# schematic.net
KiCad netlist of a schematic drawn in EAGLE
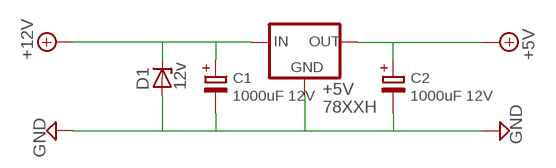
[diagram p0: schematic, sheet 1]

(export (version "E")
  (design (tool "Eeschema 10.0.6"))
  (components
    (comp (ref "+5V")
      (value "78XXH")
      (footprint "eagle-import:TO220BH")
      (libsource (lib "eagle-import") (part "78XXH"))
    )
    (comp (ref "C1")
      (value "1000uF 12V")
      (footprint "eagle-import:CAPD10L5")
      (libsource (lib "eagle-import") (part "CAPD10L5"))
    )
    (comp (ref "C2")
      (value "1000uF 12V")
      (footprint "eagle-import:CAPD10L5")
      (libsource (lib "eagle-import") (part "CAPD10L5"))
    )
    (comp (ref "D1")
      (value "12v")
      (footprint "eagle-import:DO34Z7")
      (libsource (lib "eagle-import") (part "ZENER-DIODEDO34-7"))
    )
  )
  (nets
    (net (code "1") (name "+5V") (class "Default")
      (node (ref "+5V") (pin "S") (pinfunction "OUT_S") (pintype "passive"))
      (node (ref "C2") (pin "1") (pinfunction "+_1") (pintype "passive"))
    )
    (net (code "2") (name "+12V") (class "Default")
      (node (ref "+5V") (pin "G") (pinfunction "IN_G") (pintype "passive"))
    )
    (net (code "4") (name "unconnected-(+5V-GND-PadD)") (class "Default")
      (node (ref "+5V") (pin "D") (pinfunction "GND_D") (pintype "passive"))
    )
    (net (code "5") (name "unconnected-(C1-+-Pad1)") (class "Default")
      (node (ref "C1") (pin "1") (pinfunction "+_1") (pintype "passive"))
    )
    (net (code "6") (name "unconnected-(C1---Pad2)") (class "Default")
      (node (ref "C1") (pin "2") (pinfunction "-_2") (pintype "passive"))
    )
    (net (code "7") (name "unconnected-(C2---Pad2)") (class "Default")
      (node (ref "C2") (pin "2") (pinfunction "-_2") (pintype "passive"))
    )
    (net (code "8") (name "unconnected-(D1-PadA)") (class "Default")
      (node (ref "D1") (pin "A") (pinfunction "A_A") (pintype "passive"))
    )
    (net (code "9") (name "unconnected-(D1-PadC)") (class "Default")
      (node (ref "D1") (pin "C") (pinfunction "C_C") (pintype "passive"))
    )
  )
)
